# Curios.net
KiCad netlist of a schematic drawn in EAGLE
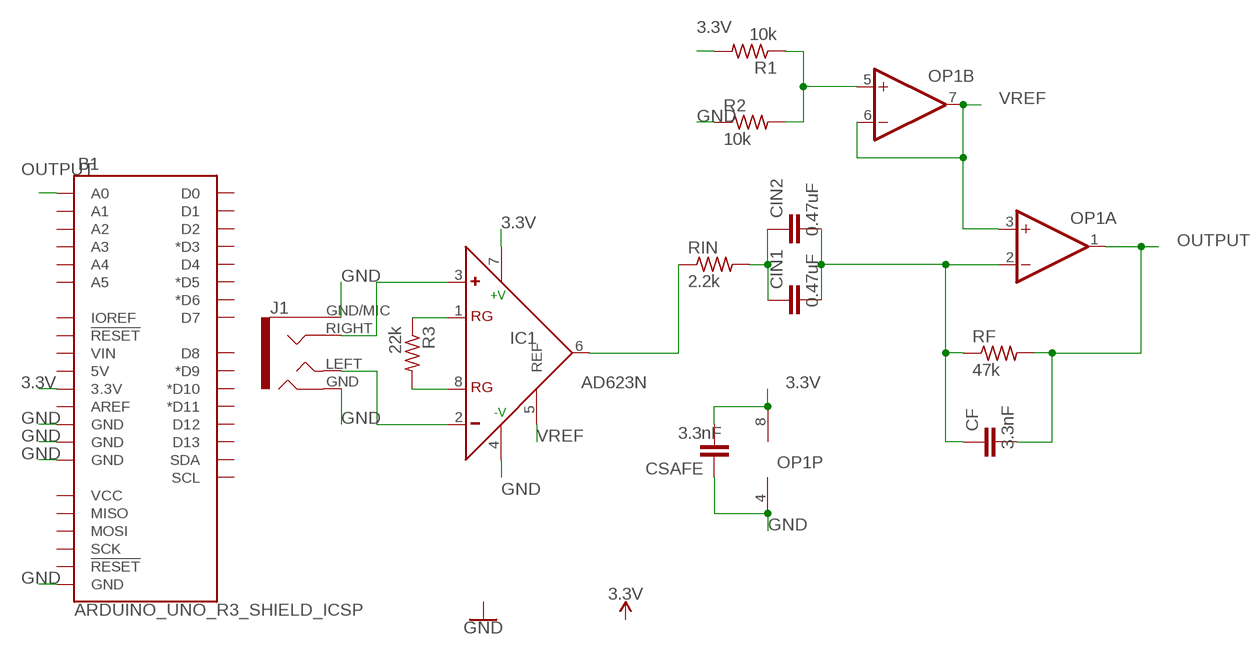
[diagram p0: schematic, sheet 1]

(export (version "E")
  (design (tool "Eeschema 10.0.6"))
  (components
    (comp (ref "B1")
      (value "ARDUINO_UNO_R3_SHIELD_ICSP")
      (footprint "eagle-import:UNO_R3_SHIELD_ICSP")
      (libsource (lib "eagle-import") (part "ARDUINO_UNO_R3_SHIELD_ICSP"))
    )
    (comp (ref "CF")
      (value "3.3nF")
      (footprint "eagle-import:C0603")
      (libsource (lib "eagle-import") (part "CAPACITOR0603"))
    )
    (comp (ref "CIN1")
      (value "0.47uF")
      (footprint "eagle-import:C0603")
      (libsource (lib "eagle-import") (part "CAPACITOR0603"))
    )
    (comp (ref "CIN2")
      (value "0.47uF")
      (footprint "eagle-import:C0603")
      (libsource (lib "eagle-import") (part "CAPACITOR0603"))
    )
    (comp (ref "CSAFE")
      (value "3.3nF")
      (footprint "eagle-import:C0603")
      (libsource (lib "eagle-import") (part "CAPACITOR0603"))
    )
    (comp (ref "IC1")
      (value "AD623N")
      (footprint "eagle-import:DIL08")
      (fields (field (name "MF") "ALTERA CORPORATION") (field (name "MPN") "AD623ANZ"))
      (libsource (lib "eagle-import") (part "AD623N"))
    )
    (comp (ref "J1")
      (value "AUDIO_JACK_TRRSSMD_RA")
      (footprint "eagle-import:AUDIO_JACK_3.5MM_TRRS_SMD_RA")
      (libsource (lib "eagle-import") (part "AUDIO_JACK_TRRSSMD_RA"))
    )
    (comp (ref "OP1")
      (value "OP-DUALR")
      (footprint "eagle-import:SO8")
      (fields (field (name "MPN") "AD8607ARMZ-R2"))
      (libsource (lib "eagle-import") (part "OP-DUALR"))
    )
    (comp (ref "R1")
      (value "10k")
      (footprint "eagle-import:R0603")
      (libsource (lib "eagle-import") (part "RESISTOR0603"))
    )
    (comp (ref "R2")
      (value "10k")
      (footprint "eagle-import:R0603")
      (libsource (lib "eagle-import") (part "RESISTOR0603"))
    )
    (comp (ref "R3")
      (value "22k")
      (footprint "eagle-import:R0603")
      (libsource (lib "eagle-import") (part "RESISTOR0603"))
    )
    (comp (ref "RF")
      (value "47k")
      (footprint "eagle-import:R0603")
      (libsource (lib "eagle-import") (part "RESISTOR0603"))
    )
    (comp (ref "RIN")
      (value "2.2k")
      (footprint "eagle-import:R0603")
      (libsource (lib "eagle-import") (part "RESISTOR0603"))
    )
  )
  (nets
    (net (code "1") (name "/OUTPUT") (class "Default")
      (node (ref "B1") (pin "A0") (pinfunction "A0_A0") (pintype "bidirectional"))
      (node (ref "CF") (pin "2") (pinfunction "2_2") (pintype "passive"))
      (node (ref "OP1") (pin "1") (pinfunction "OUT_1") (pintype "output"))
      (node (ref "RF") (pin "2") (pinfunction "2_2") (pintype "passive"))
    )
    (net (code "2") (name "/VREF") (class "Default")
      (node (ref "IC1") (pin "5") (pinfunction "REF_5") (pintype "passive"))
      (node (ref "OP1") (pin "3") (pinfunction "+IN_3") (pintype "input"))
      (node (ref "OP1") (pin "6") (pinfunction "-IN_6") (pintype "input"))
      (node (ref "OP1") (pin "7") (pinfunction "OUT_7") (pintype "output"))
    )
    (net (code "3") (name "3.3V") (class "Default")
      (node (ref "B1") (pin "3.3V") (pinfunction "3.3V_3.3V") (pintype "bidirectional"))
      (node (ref "CSAFE") (pin "2") (pinfunction "2_2") (pintype "passive"))
      (node (ref "IC1") (pin "7") (pinfunction "+V_7") (pintype "power_in"))
      (node (ref "OP1") (pin "8") (pinfunction "V+_8") (pintype "power_in"))
      (node (ref "R1") (pin "2") (pinfunction "2_2") (pintype "passive"))
    )
    (net (code "4") (name "GND") (class "Default")
      (node (ref "B1") (pin "GND@0") (pinfunction "GND_GND@0") (pintype "bidirectional"))
      (node (ref "B1") (pin "GND@1") (pinfunction "GND_GND@1") (pintype "bidirectional"))
      (node (ref "B1") (pin "GND@2") (pinfunction "GND_GND@2") (pintype "bidirectional"))
      (node (ref "B1") (pin "GND_ICSP") (pinfunction "GND_GND_ICSP") (pintype "bidirectional"))
      (node (ref "CSAFE") (pin "1") (pinfunction "1_1") (pintype "passive"))
      (node (ref "IC1") (pin "4") (pinfunction "-V_4") (pintype "power_in"))
      (node (ref "J1") (pin "GND") (pinfunction "RING2_GND") (pintype "bidirectional"))
      (node (ref "J1") (pin "GND/MIC") (pinfunction "SLEEVE_GND/MIC") (pintype "bidirectional"))
      (node (ref "OP1") (pin "4") (pinfunction "V-_4") (pintype "power_in"))
      (node (ref "R2") (pin "1") (pinfunction "1_1") (pintype "passive"))
    )
    (net (code "5") (name "Net-(CIN1-Pad1)") (class "Default")
      (node (ref "CIN1") (pin "1") (pinfunction "1_1") (pintype "passive"))
      (node (ref "CIN2") (pin "1") (pinfunction "1_1") (pintype "passive"))
      (node (ref "RIN") (pin "2") (pinfunction "2_2") (pintype "passive"))
    )
    (net (code "6") (name "Net-(IC1-+)") (class "Default")
      (node (ref "IC1") (pin "3") (pinfunction "+_3") (pintype "input"))
      (node (ref "J1") (pin "RIGHT") (pinfunction "RING1_RIGHT") (pintype "bidirectional"))
    )
    (net (code "7") (name "Net-(IC1--)") (class "Default")
      (node (ref "IC1") (pin "2") (pinfunction "-_2") (pintype "input"))
      (node (ref "J1") (pin "LEFT") (pinfunction "TIP_LEFT") (pintype "bidirectional"))
    )
    (net (code "8") (name "Net-(IC1-OUT)") (class "Default")
      (node (ref "IC1") (pin "6") (pinfunction "OUT_6") (pintype "output"))
      (node (ref "RIN") (pin "1") (pinfunction "1_1") (pintype "passive"))
    )
    (net (code "9") (name "Net-(IC1-RG-Pad1)") (class "Default")
      (node (ref "IC1") (pin "1") (pinfunction "RG_1") (pintype "passive"))
      (node (ref "R3") (pin "1") (pinfunction "1_1") (pintype "passive"))
    )
    (net (code "10") (name "Net-(IC1-RG-Pad8)") (class "Default")
      (node (ref "IC1") (pin "8") (pinfunction "RG_8") (pintype "passive"))
      (node (ref "R3") (pin "2") (pinfunction "2_2") (pintype "passive"))
    )
    (net (code "11") (name "Net-(OP1A--IN)") (class "Default")
      (node (ref "CF") (pin "1") (pinfunction "1_1") (pintype "passive"))
      (node (ref "CIN1") (pin "2") (pinfunction "2_2") (pintype "passive"))
      (node (ref "CIN2") (pin "2") (pinfunction "2_2") (pintype "passive"))
      (node (ref "OP1") (pin "2") (pinfunction "-IN_2") (pintype "input"))
      (node (ref "RF") (pin "1") (pinfunction "1_1") (pintype "passive"))
    )
    (net (code "12") (name "Net-(OP1B-+IN)") (class "Default")
      (node (ref "OP1") (pin "5") (pinfunction "+IN_5") (pintype "input"))
      (node (ref "R1") (pin "1") (pinfunction "1_1") (pintype "passive"))
      (node (ref "R2") (pin "2") (pinfunction "2_2") (pintype "passive"))
    )
    (net (code "13") (name "unconnected-(B1-*D3-PadD3)") (class "Default")
      (node (ref "B1") (pin "D3") (pinfunction "*D3_D3") (pintype "bidirectional"))
    )
    (net (code "14") (name "unconnected-(B1-*D5-PadD5)") (class "Default")
      (node (ref "B1") (pin "D5") (pinfunction "*D5_D5") (pintype "bidirectional"))
    )
    (net (code "15") (name "unconnected-(B1-*D6-PadD6)") (class "Default")
      (node (ref "B1") (pin "D6") (pinfunction "*D6_D6") (pintype "bidirectional"))
    )
    (net (code "16") (name "unconnected-(B1-*D9-PadD9)") (class "Default")
      (node (ref "B1") (pin "D9") (pinfunction "*D9_D9") (pintype "bidirectional"))
    )
    (net (code "17") (name "unconnected-(B1-*D10-PadD10)") (class "Default")
      (node (ref "B1") (pin "D10") (pinfunction "*D10_D10") (pintype "bidirectional"))
    )
    (net (code "18") (name "unconnected-(B1-*D11-PadD11)") (class "Default")
      (node (ref "B1") (pin "D11") (pinfunction "*D11_D11") (pintype "bidirectional"))
    )
    (net (code "19") (name "unconnected-(B1-D0-PadRX)") (class "Default")
      (node (ref "B1") (pin "RX") (pinfunction "D0_RX") (pintype "bidirectional"))
    )
    (net (code "20") (name "unconnected-(B1-D1-PadTX)") (class "Default")
      (node (ref "B1") (pin "TX") (pinfunction "D1_TX") (pintype "bidirectional"))
    )
    (net (code "21") (name "unconnected-(B1-Pad5V)") (class "Default")
      (node (ref "B1") (pin "5V") (pinfunction "5V_5V") (pintype "bidirectional"))
    )
    (net (code "22") (name "unconnected-(B1-PadA1)") (class "Default")
      (node (ref "B1") (pin "A1") (pinfunction "A1_A1") (pintype "bidirectional"))
    )
    (net (code "23") (name "unconnected-(B1-PadA2)") (class "Default")
      (node (ref "B1") (pin "A2") (pinfunction "A2_A2") (pintype "bidirectional"))
    )
    (net (code "24") (name "unconnected-(B1-PadA3)") (class "Default")
      (node (ref "B1") (pin "A3") (pinfunction "A3_A3") (pintype "bidirectional"))
    )
    (net (code "25") (name "unconnected-(B1-PadA4)") (class "Default")
      (node (ref "B1") (pin "A4") (pinfunction "A4_A4") (pintype "bidirectional"))
    )
    (net (code "26") (name "unconnected-(B1-PadA5)") (class "Default")
      (node (ref "B1") (pin "A5") (pinfunction "A5_A5") (pintype "bidirectional"))
    )
    (net (code "27") (name "unconnected-(B1-PadAREF)") (class "Default")
      (node (ref "B1") (pin "AREF") (pinfunction "AREF_AREF") (pintype "bidirectional"))
    )
    (net (code "28") (name "unconnected-(B1-PadD2)") (class "Default")
      (node (ref "B1") (pin "D2") (pinfunction "D2_D2") (pintype "bidirectional"))
    )
    (net (code "29") (name "unconnected-(B1-PadD4)") (class "Default")
      (node (ref "B1") (pin "D4") (pinfunction "D4_D4") (pintype "bidirectional"))
    )
    (net (code "30") (name "unconnected-(B1-PadD7)") (class "Default")
      (node (ref "B1") (pin "D7") (pinfunction "D7_D7") (pintype "bidirectional"))
    )
    (net (code "31") (name "unconnected-(B1-PadD8)") (class "Default")
      (node (ref "B1") (pin "D8") (pinfunction "D8_D8") (pintype "bidirectional"))
    )
    (net (code "32") (name "unconnected-(B1-PadD12)") (class "Default")
      (node (ref "B1") (pin "D12") (pinfunction "D12_D12") (pintype "bidirectional"))
    )
    (net (code "33") (name "unconnected-(B1-PadD13)") (class "Default")
      (node (ref "B1") (pin "D13") (pinfunction "D13_D13") (pintype "bidirectional"))
    )
    (net (code "34") (name "unconnected-(B1-PadIOREF)") (class "Default")
      (node (ref "B1") (pin "IOREF") (pinfunction "IOREF_IOREF") (pintype "bidirectional"))
    )
    (net (code "35") (name "unconnected-(B1-PadMISO)") (class "Default")
      (node (ref "B1") (pin "MISO") (pinfunction "MISO_MISO") (pintype "bidirectional"))
    )
    (net (code "36") (name "unconnected-(B1-PadMOSI)") (class "Default")
      (node (ref "B1") (pin "MOSI") (pinfunction "MOSI_MOSI") (pintype "bidirectional"))
    )
    (net (code "37") (name "unconnected-(B1-PadSCK)") (class "Default")
      (node (ref "B1") (pin "SCK") (pinfunction "SCK_SCK") (pintype "bidirectional"))
    )
    (net (code "38") (name "unconnected-(B1-PadSCL)") (class "Default")
      (node (ref "B1") (pin "SCL") (pinfunction "SCL_SCL") (pintype "bidirectional"))
    )
    (net (code "39") (name "unconnected-(B1-PadSDA)") (class "Default")
      (node (ref "B1") (pin "SDA") (pinfunction "SDA_SDA") (pintype "bidirectional"))
    )
    (net (code "40") (name "unconnected-(B1-PadVIN)") (class "Default")
      (node (ref "B1") (pin "VIN") (pinfunction "VIN_VIN") (pintype "bidirectional"))
    )
    (net (code "41") (name "unconnected-(B1-VCC-Pad5V_ICSP)") (class "Default")
      (node (ref "B1") (pin "5V_ICSP") (pinfunction "VCC_5V_ICSP") (pintype "bidirectional"))
    )
    (net (code "42") (name "unconnected-(B1-~{RESET}-PadRES)") (class "Default")
      (node (ref "B1") (pin "RES") (pinfunction "~{RESET}_RES") (pintype "bidirectional"))
    )
    (net (code "43") (name "unconnected-(B1-~{RESET}-PadRST_ICSP)") (class "Default")
      (node (ref "B1") (pin "RST_ICSP") (pinfunction "~{RESET}_RST_ICSP") (pintype "bidirectional"))
    )
  )
)
